# CAN.net
KiCad netlist of a schematic drawn in Altium Designer
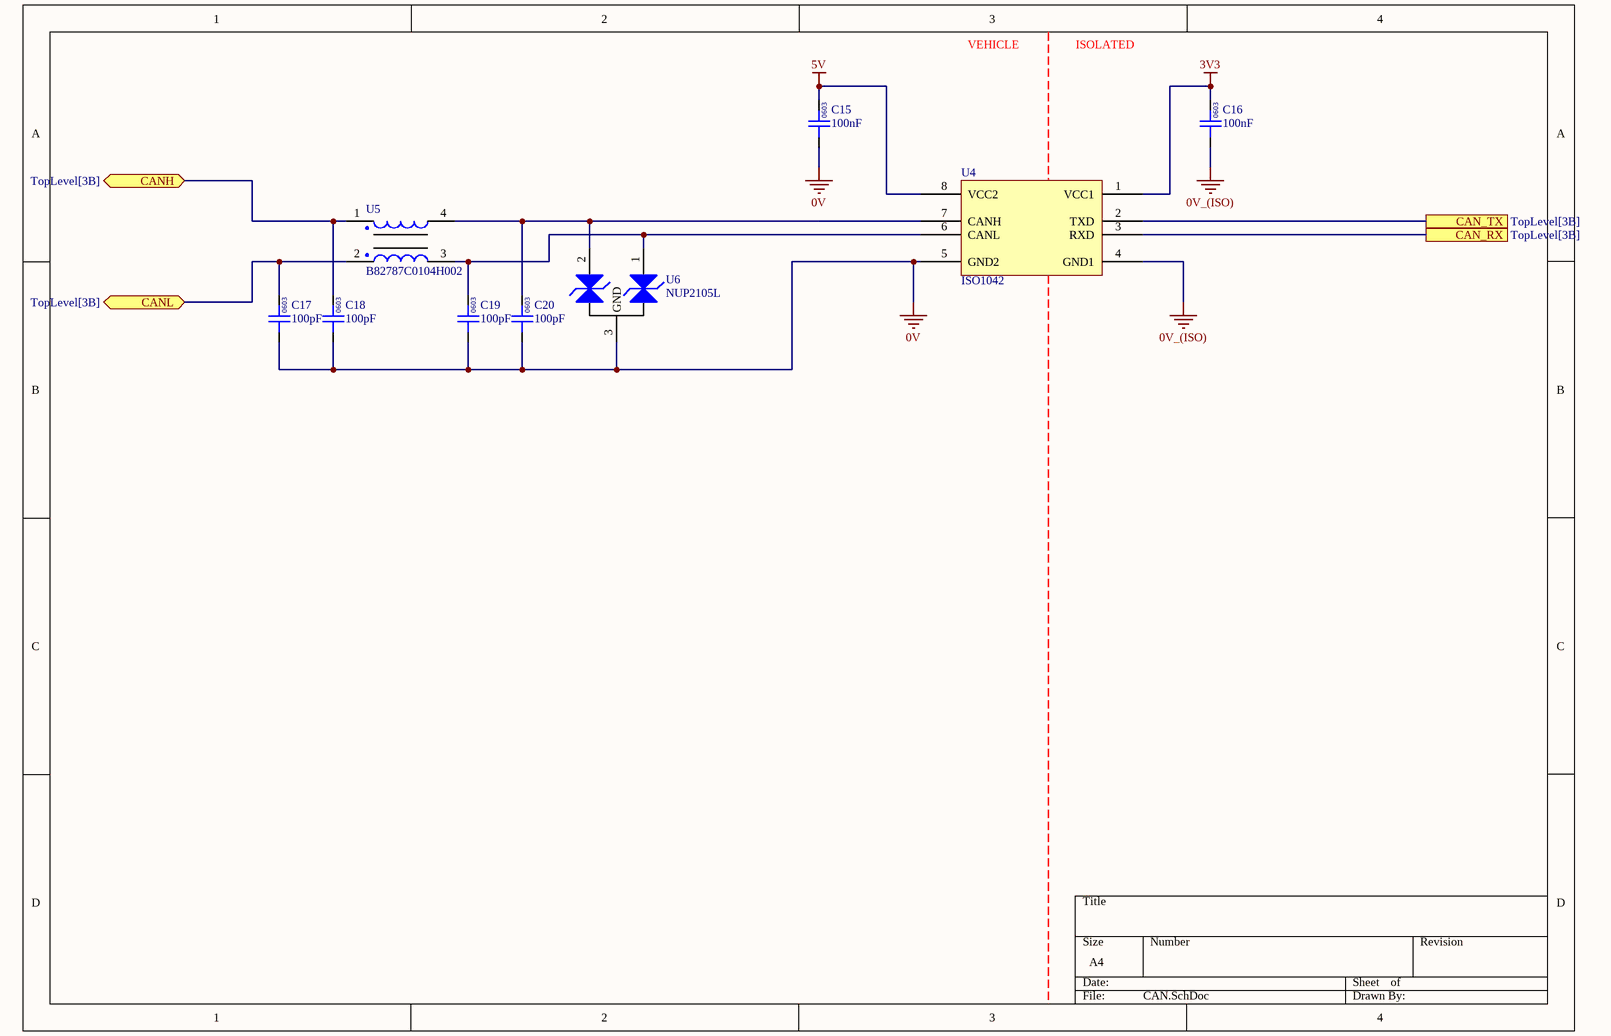
[diagram p0: CAN.SchDoc]

(export (version "E")
  (design (tool "Eeschema 10.0.6"))
  (components
    (comp (ref "C15")
      (value "100nF")
      (footprint "0603")
      (fields
        (field (name "PART NUMBER") "GCM188L81H104KA57D")
        (field (name "MANUFACTURER") "muRata")
        (field (name "TOLERANCE") "±10%")
      )
      (libsource (lib "ts_standard_library") (part "Capacitor 0603"))
    )
    (comp (ref "C16")
      (value "100nF")
      (footprint "0603")
      (fields
        (field (name "PART NUMBER") "GCM188L81H104KA57D")
        (field (name "MANUFACTURER") "muRata")
        (field (name "TOLERANCE") "±10%")
      )
      (libsource (lib "ts_standard_library") (part "Capacitor 0603"))
    )
    (comp (ref "C17")
      (value "100pF")
      (footprint "0603")
      (fields
        (field (name "PART NUMBER") "GRM1885C1H101JA01D")
        (field (name "MANUFACTURER") "Murata Electronics")
        (field (name "TOLERANCE") "±5%")
      )
      (libsource (lib "ts_standard_library") (part "Capacitor 0603"))
    )
    (comp (ref "C18")
      (value "100pF")
      (footprint "0603")
      (fields
        (field (name "PART NUMBER") "GRM1885C1H101JA01D")
        (field (name "MANUFACTURER") "Murata Electronics")
        (field (name "TOLERANCE") "±5%")
      )
      (libsource (lib "ts_standard_library") (part "Capacitor 0603"))
    )
    (comp (ref "C19")
      (value "100pF")
      (footprint "0603")
      (fields
        (field (name "PART NUMBER") "GRM1885C1H101JA01D")
        (field (name "MANUFACTURER") "Murata Electronics")
        (field (name "TOLERANCE") "±5%")
      )
      (libsource (lib "ts_standard_library") (part "Capacitor 0603"))
    )
    (comp (ref "C20")
      (value "100pF")
      (footprint "0603")
      (fields
        (field (name "PART NUMBER") "GRM1885C1H101JA01D")
        (field (name "MANUFACTURER") "Murata Electronics")
        (field (name "TOLERANCE") "±5%")
      )
      (libsource (lib "ts_standard_library") (part "Capacitor 0603"))
    )
    (comp (ref "U4")
      (value "ISO1042")
      (footprint "TI-SOIC-8")
      (description "IC CAN TRANSCEIVER 1/1 8SOIC")
      (fields
        (field (name "MANUFACTURER") "Texas Instruments")
        (field (name "DIGIKEY PART NUMBER") "296-ISO1042BQDWVQ1-ND")
      )
      (libsource (lib "ts_standard_library") (part "ISO1042"))
    )
    (comp (ref "U5")
      (value "B82787C0104H002")
      (footprint "TDK 4-PC Pad")
      (fields
        (field (name "MANUFACTURER") "EPCOS (TDK)")
        (field (name "DIGIKEY PART NUMBER") "495-4598-1-ND")
      )
      (libsource (lib "ts_standard_library") (part "B82787C0104H002"))
    )
    (comp (ref "U6")
      (value "NUP2105L")
      (footprint "ON SOT-23")
      (description "Dual Line CAN Bus Protector")
      (fields
        (field (name "MANUFACTURER") "ON Semiconductor")
        (field (name "DIGIKEY PART NUMBER") "NUP2105LT1GOSCT-ND")
      )
      (libsource (lib "ts_standard_library") (part "NUP2105L"))
    )
  )
  (nets
    (net (code "1") (name "/CANH") (class "Default")
      (node (ref "C18") (pin "2") (pinfunction "2_2") (pintype "passive"))
      (node (ref "U5") (pin "1") (pinfunction "1_1") (pintype "passive"))
    )
    (net (code "2") (name "/CANL") (class "Default")
      (node (ref "C17") (pin "2") (pinfunction "2_2") (pintype "passive"))
      (node (ref "U5") (pin "2") (pinfunction "2_2") (pintype "passive"))
    )
    (net (code "3") (name "/CAN_RX") (class "Default")
      (node (ref "U4") (pin "3") (pinfunction "RXD_3") (pintype "passive"))
    )
    (net (code "4") (name "/CAN_TX") (class "Default")
      (node (ref "U4") (pin "2") (pinfunction "TXD_2") (pintype "passive"))
    )
    (net (code "5") (name "0V") (class "Default")
      (node (ref "C15") (pin "1") (pinfunction "1_1") (pintype "passive"))
      (node (ref "C17") (pin "1") (pinfunction "1_1") (pintype "passive"))
      (node (ref "C18") (pin "1") (pinfunction "1_1") (pintype "passive"))
      (node (ref "C19") (pin "1") (pinfunction "1_1") (pintype "passive"))
      (node (ref "C20") (pin "1") (pinfunction "1_1") (pintype "passive"))
      (node (ref "U4") (pin "5") (pinfunction "GND2_5") (pintype "passive"))
      (node (ref "U6") (pin "3") (pinfunction "GND_3") (pintype "passive"))
    )
    (net (code "6") (name "0V_(ISO)") (class "Default")
      (node (ref "C16") (pin "1") (pinfunction "1_1") (pintype "passive"))
      (node (ref "U4") (pin "4") (pinfunction "GND1_4") (pintype "passive"))
    )
    (net (code "7") (name "3V3") (class "Default")
      (node (ref "C16") (pin "2") (pinfunction "2_2") (pintype "passive"))
      (node (ref "U4") (pin "1") (pinfunction "VCC1_1") (pintype "passive"))
    )
    (net (code "8") (name "5V") (class "Default")
      (node (ref "C15") (pin "2") (pinfunction "2_2") (pintype "passive"))
      (node (ref "U4") (pin "8") (pinfunction "VCC2_8") (pintype "passive"))
    )
    (net (code "9") (name "Net-(U4-CANH)") (class "Default")
      (node (ref "C20") (pin "2") (pinfunction "2_2") (pintype "passive"))
      (node (ref "U4") (pin "7") (pinfunction "CANH_7") (pintype "passive"))
      (node (ref "U5") (pin "4") (pinfunction "4_4") (pintype "passive"))
      (node (ref "U6") (pin "2") (pinfunction "CAN_L_2") (pintype "passive"))
    )
    (net (code "10") (name "Net-(U4-CANL)") (class "Default")
      (node (ref "C19") (pin "2") (pinfunction "2_2") (pintype "passive"))
      (node (ref "U4") (pin "6") (pinfunction "CANL_6") (pintype "passive"))
      (node (ref "U5") (pin "3") (pinfunction "3_3") (pintype "passive"))
      (node (ref "U6") (pin "1") (pinfunction "CAN_H_1") (pintype "passive"))
    )
  )
)
